# design.net
KiCad netlist of a schematic drawn in Altium Designer
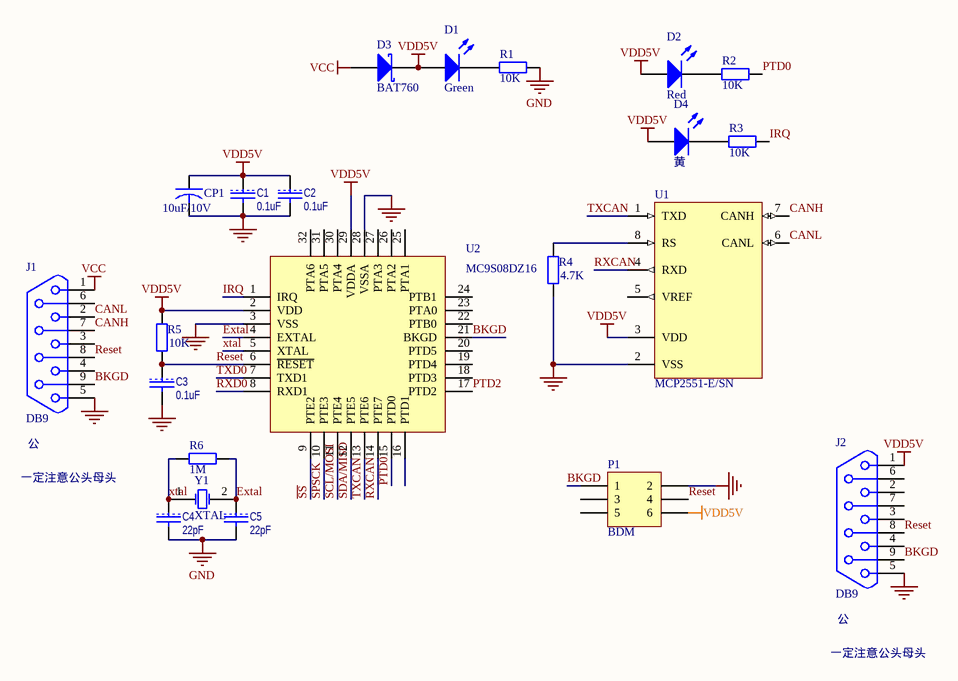
[diagram p0: 加密狗第五版.SchDoc]

(export (version "E")
  (design (tool "Eeschema 10.0.6"))
  (components
    (comp (ref "C1")
      (value "0.1uF")
      (footprint "1608[0603]")
      (description "Capacitor")
      (libsource (lib "*") (part "CAP"))
    )
    (comp (ref "C2")
      (value "0.1uF")
      (footprint "1608[0603]")
      (description "Capacitor")
      (libsource (lib "*") (part "CAP"))
    )
    (comp (ref "C3")
      (value "0.1uF")
      (footprint "1608[0603]")
      (description "Capacitor")
      (libsource (lib "*") (part "CAP"))
    )
    (comp (ref "C4")
      (value "22pF")
      (footprint "1608[0603]")
      (description "Capacitor")
      (libsource (lib "*") (part "CAP"))
    )
    (comp (ref "C5")
      (value "22pF")
      (footprint "1608[0603]")
      (description "Capacitor")
      (libsource (lib "*") (part "CAP"))
    )
    (comp (ref "CP1")
      (value "10uF/10V")
      (footprint "C1206")
      (description "Capacitor")
      (libsource (lib "*") (part "CAPACITOR"))
    )
    (comp (ref "D1")
      (value "Green")
      (footprint "LED")
      (description "Typical RED, GREEN, YELLOW, AMBER GaAs LED")
      (fields (field (name "PUBLISHER") "Altium Limited"))
      (libsource (lib "Miscellaneous Devices") (part "LED2"))
    )
    (comp (ref "D2")
      (value "Red")
      (footprint "LED")
      (description "Typical RED, GREEN, YELLOW, AMBER GaAs LED")
      (fields (field (name "PUBLISHER") "Altium Limited"))
      (libsource (lib "Miscellaneous Devices") (part "LED2"))
    )
    (comp (ref "D3")
      (value "BAT760")
      (footprint "SOD323")
      (description "Schottky Barrier Diode")
      (fields (field (name "PUBLISHER") "Altium Limited"))
      (libsource (lib "Philips Discrete Diode - Schottky") (part "BAT760"))
    )
    (comp (ref "D4")
      (value "黄")
      (footprint "LED")
      (description "Typical RED, GREEN, YELLOW, AMBER GaAs LED")
      (fields (field (name "PUBLISHER") "Altium Limited"))
      (libsource (lib "Miscellaneous Devices") (part "LED2"))
    )
    (comp (ref "J1") (value "DB9") (footprint "DB9Male") (libsource (lib "*") (part "DB9")))
    (comp (ref "J2") (value "DB9") (footprint "DB9Female") (libsource (lib "*") (part "DB9")))
    (comp (ref "P1")
      (value "BDM")
      (footprint "HDR2X3")
      (description "Header, 3-Pin, Dual row")
      (fields (field (name "PUBLISHER") "Altium Limited"))
      (libsource (lib "Miscellaneous Connectors") (part "Header 3X2"))
    )
    (comp (ref "R1")
      (value "10K")
      (footprint "1608[0603] -R")
      (description "Resistor")
      (fields (field (name "Comment") "Res2") (field (name "PUBLISHER") "Altium Limited"))
      (libsource (lib "Miscellaneous Devices") (part "Res2"))
    )
    (comp (ref "R2")
      (value "10K")
      (footprint "1608[0603] -R")
      (description "Resistor")
      (fields (field (name "Comment") "Res2") (field (name "PUBLISHER") "Altium Limited"))
      (libsource (lib "Miscellaneous Devices") (part "Res2"))
    )
    (comp (ref "R3")
      (value "10K")
      (footprint "1608[0603] -R")
      (description "Resistor")
      (fields (field (name "Comment") "Res2") (field (name "PUBLISHER") "Altium Limited"))
      (libsource (lib "Miscellaneous Devices") (part "Res2"))
    )
    (comp (ref "R4")
      (value "4.7K")
      (footprint "1608[0603] -R")
      (description "Resistor")
      (fields (field (name "Comment") "Res2") (field (name "PUBLISHER") "Altium Limited"))
      (libsource (lib "") (part "Res2_1"))
    )
    (comp (ref "R5")
      (value "10K")
      (footprint "1608[0603] -R")
      (description "Resistor")
      (fields (field (name "Comment") "Res2") (field (name "PUBLISHER") "Altium Limited"))
      (libsource (lib "") (part "Res2_1"))
    )
    (comp (ref "R6")
      (value "1M")
      (footprint "1608[0603] -R")
      (description "Resistor")
      (fields (field (name "Comment") "Res2") (field (name "PUBLISHER") "Altium Limited"))
      (libsource (lib "Miscellaneous Devices") (part "Res2"))
    )
    (comp (ref "U1")
      (value "MCP2551-E/SN")
      (footprint "SOIC-SN8_N")
      (description "High-Speed CAN Transceiver, 8-Pin SOIC, Extended Temperature")
      (fields (field (name "PUBLISHER") "Altium Limited"))
      (libsource (lib "Microchip Interface") (part "MCP2551-E/SN"))
    )
    (comp (ref "U2") (value "MC9S08DZ16") (footprint "LQFP-32_N") (libsource (lib "*") (part "MC9S08DZ60")))
    (comp (ref "Y1")
      (value "XTAL")
      (footprint "BCY-F2/Z13")
      (description "Crystal Oscillator")
      (fields (field (name "PUBLISHER") "Altium Limited"))
      (libsource (lib "Miscellaneous Devices") (part "XTAL"))
    )
  )
  (nets
    (net (code "1") (name "/BKGD") (class "Default")
      (node (ref "J1") (pin "9") (pinfunction "9_9") (pintype "passive"))
      (node (ref "J2") (pin "9") (pinfunction "9_9") (pintype "passive"))
      (node (ref "P1") (pin "1") (pinfunction "1_1") (pintype "passive"))
      (node (ref "U2") (pin "21") (pinfunction "BKGD_21") (pintype "passive"))
    )
    (net (code "2") (name "/CANH") (class "Default")
      (node (ref "J1") (pin "7") (pinfunction "7_7") (pintype "passive"))
      (node (ref "U1") (pin "7") (pinfunction "CANH_7") (pintype "bidirectional"))
    )
    (net (code "3") (name "/CANL") (class "Default")
      (node (ref "J1") (pin "2") (pinfunction "2_2") (pintype "passive"))
      (node (ref "U1") (pin "6") (pinfunction "CANL_6") (pintype "bidirectional"))
    )
    (net (code "4") (name "/Extal") (class "Default")
      (node (ref "C5") (pin "1") (pinfunction "1_1") (pintype "passive"))
      (node (ref "R6") (pin "1") (pinfunction "1_1") (pintype "passive"))
      (node (ref "U2") (pin "4") (pinfunction "EXTAL_4") (pintype "passive"))
      (node (ref "Y1") (pin "2") (pinfunction "OSC2_2") (pintype "passive"))
    )
    (net (code "5") (name "/IRQ") (class "Default")
      (node (ref "R3") (pin "1") (pinfunction "1_1") (pintype "passive"))
      (node (ref "U2") (pin "1") (pinfunction "IRQ_1") (pintype "passive"))
    )
    (net (code "6") (name "/PTD0") (class "Default")
      (node (ref "R2") (pin "1") (pinfunction "1_1") (pintype "passive"))
      (node (ref "U2") (pin "15") (pinfunction "PTD0_15") (pintype "passive"))
    )
    (net (code "7") (name "/PTD2") (class "Default")
      (node (ref "U2") (pin "17") (pinfunction "PTD2_17") (pintype "passive"))
    )
    (net (code "8") (name "/RXCAN") (class "Default")
      (node (ref "U1") (pin "4") (pinfunction "RXD_4") (pintype "output"))
      (node (ref "U2") (pin "14") (pinfunction "PTE7_14") (pintype "passive"))
    )
    (net (code "9") (name "/RXD0") (class "Default")
      (node (ref "U2") (pin "8") (pinfunction "RXD1_8") (pintype "passive"))
    )
    (net (code "10") (name "/Reset") (class "Default")
      (node (ref "C3") (pin "1") (pinfunction "1_1") (pintype "passive"))
      (node (ref "J1") (pin "8") (pinfunction "8_8") (pintype "passive"))
      (node (ref "J2") (pin "8") (pinfunction "8_8") (pintype "passive"))
      (node (ref "P1") (pin "4") (pinfunction "4_4") (pintype "passive"))
      (node (ref "R5") (pin "1") (pinfunction "1_1") (pintype "passive"))
      (node (ref "U2") (pin "6") (pinfunction "~{RESET}_6") (pintype "passive"))
    )
    (net (code "11") (name "/SCL{slash}MOSI") (class "Default")
      (node (ref "U2") (pin "11") (pinfunction "PTE4_11") (pintype "passive"))
    )
    (net (code "12") (name "/SDA{slash}MISO") (class "Default")
      (node (ref "U2") (pin "12") (pinfunction "PTE5_12") (pintype "passive"))
    )
    (net (code "13") (name "/SPSCK") (class "Default")
      (node (ref "U2") (pin "10") (pinfunction "PTE3_10") (pintype "passive"))
    )
    (net (code "14") (name "/TXCAN") (class "Default")
      (node (ref "U1") (pin "1") (pinfunction "TXD_1") (pintype "input"))
      (node (ref "U2") (pin "13") (pinfunction "PTE6_13") (pintype "passive"))
    )
    (net (code "15") (name "/TXD0") (class "Default")
      (node (ref "U2") (pin "7") (pinfunction "TXD1_7") (pintype "passive"))
    )
    (net (code "16") (name "/xtal") (class "Default")
      (node (ref "C4") (pin "1") (pinfunction "1_1") (pintype "passive"))
      (node (ref "R6") (pin "2") (pinfunction "2_2") (pintype "passive"))
      (node (ref "U2") (pin "5") (pinfunction "XTAL_5") (pintype "passive"))
      (node (ref "Y1") (pin "1") (pinfunction "OSC1_1") (pintype "passive"))
    )
    (net (code "17") (name "/~{SS}") (class "Default")
      (node (ref "U2") (pin "9") (pinfunction "PTE2_9") (pintype "passive"))
    )
    (net (code "18") (name "GND") (class "Default")
      (node (ref "C1") (pin "2") (pinfunction "2_2") (pintype "passive"))
      (node (ref "C2") (pin "2") (pinfunction "2_2") (pintype "passive"))
      (node (ref "C3") (pin "2") (pinfunction "2_2") (pintype "passive"))
      (node (ref "C4") (pin "2") (pinfunction "2_2") (pintype "passive"))
      (node (ref "C5") (pin "2") (pinfunction "2_2") (pintype "passive"))
      (node (ref "CP1") (pin "2") (pinfunction "2_2") (pintype "passive"))
      (node (ref "J1") (pin "5") (pinfunction "5_5") (pintype "passive"))
      (node (ref "J2") (pin "5") (pinfunction "5_5") (pintype "passive"))
      (node (ref "P1") (pin "2") (pinfunction "2_2") (pintype "passive"))
      (node (ref "R1") (pin "1") (pinfunction "1_1") (pintype "passive"))
      (node (ref "R4") (pin "1") (pinfunction "1_1") (pintype "passive"))
      (node (ref "U1") (pin "2") (pinfunction "VSS_2") (pintype "power_in"))
      (node (ref "U2") (pin "28") (pinfunction "VSSA_28") (pintype "passive"))
      (node (ref "U2") (pin "3") (pinfunction "VSS_3") (pintype "passive"))
    )
    (net (code "19") (name "Net-(D1-K)") (class "Default")
      (node (ref "D1") (pin "2") (pinfunction "K_2") (pintype "passive"))
      (node (ref "R1") (pin "2") (pinfunction "2_2") (pintype "passive"))
    )
    (net (code "20") (name "Net-(D2-K)") (class "Default")
      (node (ref "D2") (pin "2") (pinfunction "K_2") (pintype "passive"))
      (node (ref "R2") (pin "2") (pinfunction "2_2") (pintype "passive"))
    )
    (net (code "21") (name "Net-(D4-K)") (class "Default")
      (node (ref "D4") (pin "2") (pinfunction "K_2") (pintype "passive"))
      (node (ref "R3") (pin "2") (pinfunction "2_2") (pintype "passive"))
    )
    (net (code "22") (name "Net-(U1-RS)") (class "Default")
      (node (ref "R4") (pin "2") (pinfunction "2_2") (pintype "passive"))
      (node (ref "U1") (pin "8") (pinfunction "RS_8") (pintype "input"))
    )
    (net (code "23") (name "VCC") (class "Default")
      (node (ref "D3") (pin "2") (pinfunction "A_2") (pintype "passive"))
      (node (ref "J1") (pin "1") (pinfunction "1_1") (pintype "passive"))
    )
    (net (code "24") (name "VDD5V") (class "Default")
      (node (ref "C1") (pin "1") (pinfunction "1_1") (pintype "passive"))
      (node (ref "C2") (pin "1") (pinfunction "1_1") (pintype "passive"))
      (node (ref "CP1") (pin "1") (pinfunction "1_1") (pintype "passive"))
      (node (ref "D1") (pin "1") (pinfunction "A_1") (pintype "passive"))
      (node (ref "D2") (pin "1") (pinfunction "A_1") (pintype "passive"))
      (node (ref "D3") (pin "1") (pinfunction "K_1") (pintype "passive"))
      (node (ref "D4") (pin "1") (pinfunction "A_1") (pintype "passive"))
      (node (ref "J2") (pin "1") (pinfunction "1_1") (pintype "passive"))
      (node (ref "P1") (pin "6") (pinfunction "6_6") (pintype "passive"))
      (node (ref "R5") (pin "2") (pinfunction "2_2") (pintype "passive"))
      (node (ref "U1") (pin "3") (pinfunction "VDD_3") (pintype "power_in"))
      (node (ref "U2") (pin "2") (pinfunction "VDD_2") (pintype "passive"))
      (node (ref "U2") (pin "29") (pinfunction "VDDA_29") (pintype "passive"))
    )
    (net (code "25") (name "unconnected-(J1-Pad3)") (class "Default")
      (node (ref "J1") (pin "3") (pinfunction "3_3") (pintype "passive"))
    )
    (net (code "26") (name "unconnected-(J1-Pad4)") (class "Default")
      (node (ref "J1") (pin "4") (pinfunction "4_4") (pintype "passive"))
    )
    (net (code "27") (name "unconnected-(J1-Pad6)") (class "Default")
      (node (ref "J1") (pin "6") (pinfunction "6_6") (pintype "passive"))
    )
    (net (code "28") (name "unconnected-(J2-Pad2)") (class "Default")
      (node (ref "J2") (pin "2") (pinfunction "2_2") (pintype "passive"))
    )
    (net (code "29") (name "unconnected-(J2-Pad3)") (class "Default")
      (node (ref "J2") (pin "3") (pinfunction "3_3") (pintype "passive"))
    )
    (net (code "30") (name "unconnected-(J2-Pad4)") (class "Default")
      (node (ref "J2") (pin "4") (pinfunction "4_4") (pintype "passive"))
    )
    (net (code "31") (name "unconnected-(J2-Pad6)") (class "Default")
      (node (ref "J2") (pin "6") (pinfunction "6_6") (pintype "passive"))
    )
    (net (code "32") (name "unconnected-(J2-Pad7)") (class "Default")
      (node (ref "J2") (pin "7") (pinfunction "7_7") (pintype "passive"))
    )
    (net (code "33") (name "unconnected-(P1-Pad3)") (class "Default")
      (node (ref "P1") (pin "3") (pinfunction "3_3") (pintype "passive"))
    )
    (net (code "34") (name "unconnected-(P1-Pad5)") (class "Default")
      (node (ref "P1") (pin "5") (pinfunction "5_5") (pintype "passive"))
    )
    (net (code "35") (name "unconnected-(U1-VREF-Pad5)") (class "Default")
      (node (ref "U1") (pin "5") (pinfunction "VREF_5") (pintype "output"))
    )
    (net (code "36") (name "unconnected-(U2-PTA0-Pad23)") (class "Default")
      (node (ref "U2") (pin "23") (pinfunction "PTA0_23") (pintype "passive"))
    )
    (net (code "37") (name "unconnected-(U2-PTA1-Pad25)") (class "Default")
      (node (ref "U2") (pin "25") (pinfunction "PTA1_25") (pintype "passive"))
    )
    (net (code "38") (name "unconnected-(U2-PTA2-Pad26)") (class "Default")
      (node (ref "U2") (pin "26") (pinfunction "PTA2_26") (pintype "passive"))
    )
    (net (code "39") (name "unconnected-(U2-PTA3-Pad27)") (class "Default")
      (node (ref "U2") (pin "27") (pinfunction "PTA3_27") (pintype "passive"))
    )
    (net (code "40") (name "unconnected-(U2-PTA4-Pad30)") (class "Default")
      (node (ref "U2") (pin "30") (pinfunction "PTA4_30") (pintype "passive"))
    )
    (net (code "41") (name "unconnected-(U2-PTA5-Pad31)") (class "Default")
      (node (ref "U2") (pin "31") (pinfunction "PTA5_31") (pintype "passive"))
    )
    (net (code "42") (name "unconnected-(U2-PTA6-Pad32)") (class "Default")
      (node (ref "U2") (pin "32") (pinfunction "PTA6_32") (pintype "passive"))
    )
    (net (code "43") (name "unconnected-(U2-PTB0-Pad22)") (class "Default")
      (node (ref "U2") (pin "22") (pinfunction "PTB0_22") (pintype "passive"))
    )
    (net (code "44") (name "unconnected-(U2-PTB1-Pad24)") (class "Default")
      (node (ref "U2") (pin "24") (pinfunction "PTB1_24") (pintype "passive"))
    )
    (net (code "45") (name "unconnected-(U2-PTD1-Pad16)") (class "Default")
      (node (ref "U2") (pin "16") (pinfunction "PTD1_16") (pintype "passive"))
    )
    (net (code "46") (name "unconnected-(U2-PTD3-Pad18)") (class "Default")
      (node (ref "U2") (pin "18") (pinfunction "PTD3_18") (pintype "passive"))
    )
    (net (code "47") (name "unconnected-(U2-PTD4-Pad19)") (class "Default")
      (node (ref "U2") (pin "19") (pinfunction "PTD4_19") (pintype "passive"))
    )
    (net (code "48") (name "unconnected-(U2-PTD5-Pad20)") (class "Default")
      (node (ref "U2") (pin "20") (pinfunction "PTD5_20") (pintype "passive"))
    )
  )
)
